# ethernet.net
KiCad netlist of a schematic drawn in Altium Designer
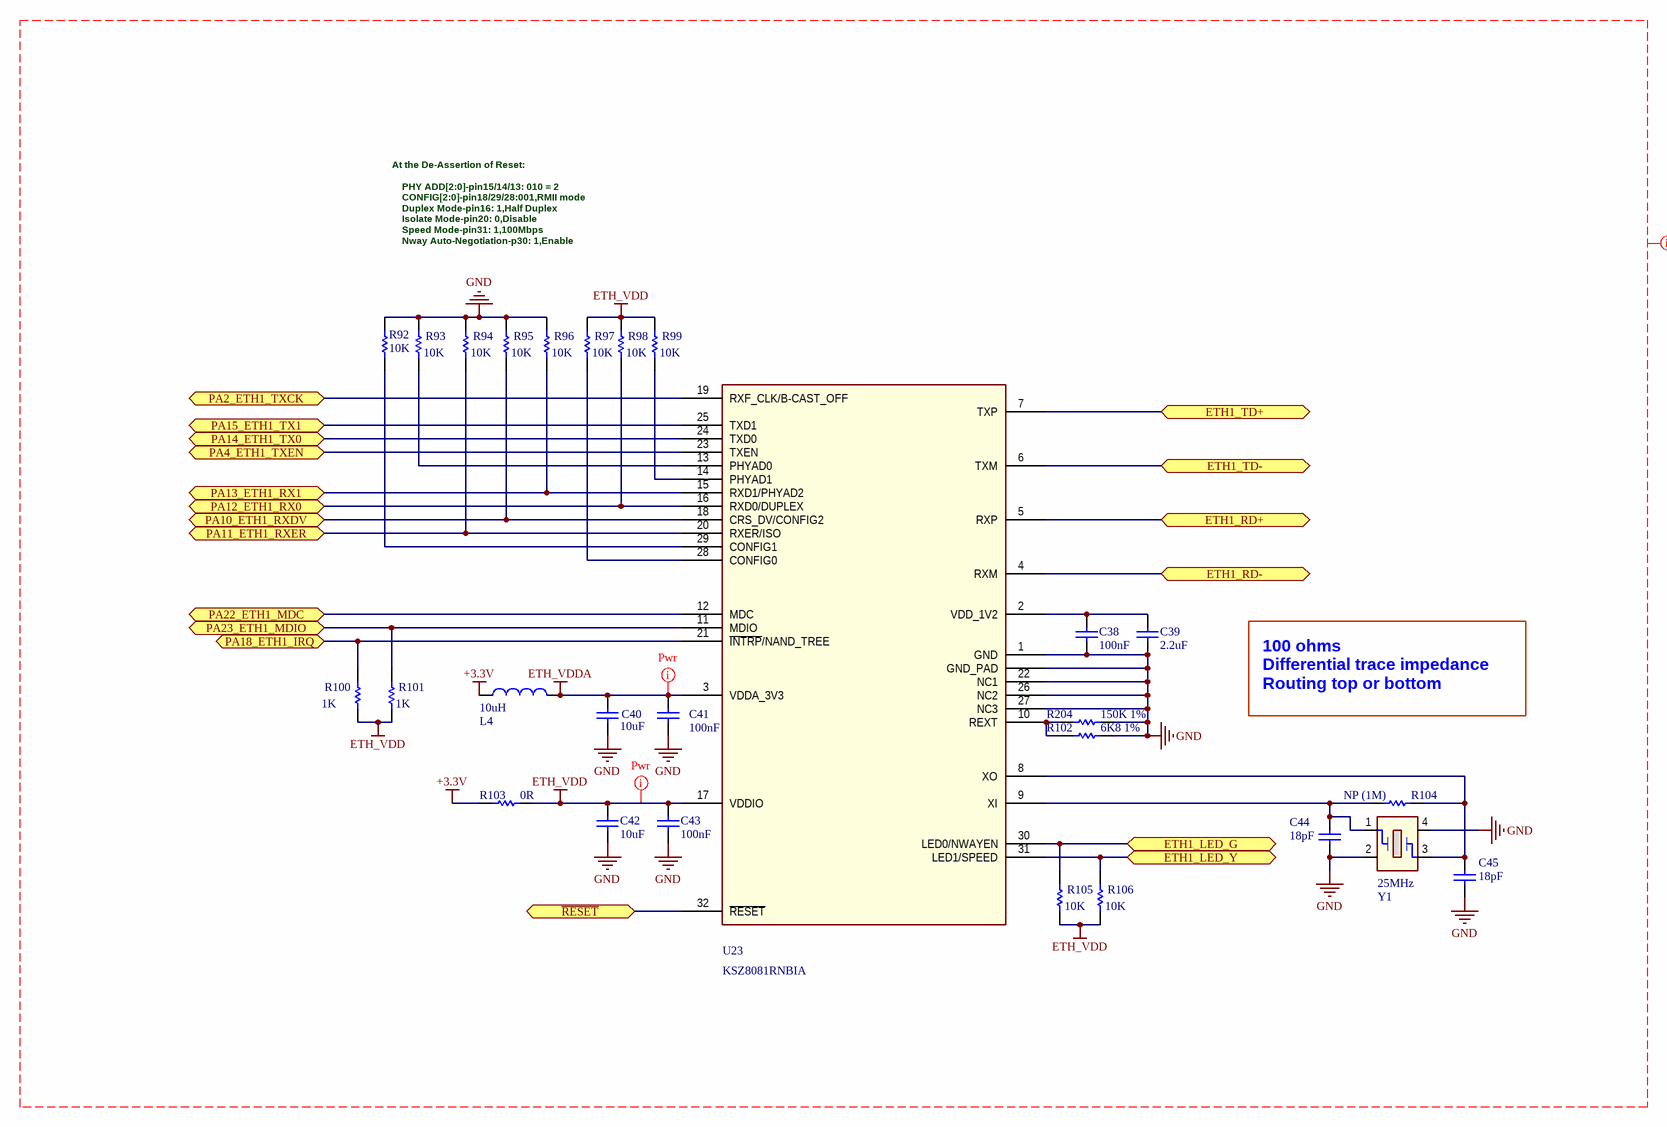
[diagram p0: ethernet.SchDoc]

(export (version "E")
  (design (tool "Eeschema 10.0.6"))
  (components
    (comp (ref "C38")
      (value "100nF")
      (footprint "0603_[1608]")
      (description "Ceramic X7R 50V")
      (fields (field (name "PUBLISHER") "Altium Limited"))
      (libsource (lib "project42_lib") (part "Cap"))
    )
    (comp (ref "C39")
      (value "2.2uF")
      (footprint "0603_[1608]")
      (description "Ceramic X7R, X5R 6.3V")
      (fields (field (name "PUBLISHER") "Altium Limited"))
      (libsource (lib "project42_lib") (part "Cap"))
    )
    (comp (ref "C40")
      (value "10uF")
      (footprint "1206_[3216]")
      (description "Ceramic X5R 25V")
      (fields (field (name "PUBLISHER") "Altium Limited"))
      (libsource (lib "project42_lib") (part "Cap"))
    )
    (comp (ref "C41")
      (value "100nF")
      (footprint "0603_[1608]")
      (description "Ceramic X7R 50V")
      (fields (field (name "PUBLISHER") "Altium Limited"))
      (libsource (lib "project42_lib") (part "Cap"))
    )
    (comp (ref "C42")
      (value "10uF")
      (footprint "1206_[3216]")
      (description "Ceramic X5R 25V")
      (fields (field (name "PUBLISHER") "Altium Limited"))
      (libsource (lib "project42_lib") (part "Cap"))
    )
    (comp (ref "C43")
      (value "100nF")
      (footprint "0603_[1608]")
      (description "Ceramic X7R 50V")
      (fields (field (name "PUBLISHER") "Altium Limited"))
      (libsource (lib "project42_lib") (part "Cap"))
    )
    (comp (ref "C44")
      (value "18pF")
      (footprint "0603_[1608]")
      (description "Ceraminc C0G/NP0 50V")
      (fields (field (name "PUBLISHER") "Altium Limited"))
      (libsource (lib "project42_lib") (part "Cap"))
    )
    (comp (ref "C45")
      (value "18pF")
      (footprint "0603_[1608]")
      (description "Ceraminc C0G/NP0 50V")
      (fields (field (name "PUBLISHER") "Altium Limited"))
      (libsource (lib "project42_lib") (part "Cap"))
    )
    (comp (ref "L4")
      (value "10uH")
      (footprint "0603_[1608]")
      (description "Inductor (MLZ1608N100L)")
      (fields (field (name "PUBLISHER") "Altium Limited"))
      (libsource (lib "DEVELER_Library") (part "Inductor"))
    )
    (comp (ref "R92")
      (value "10K")
      (footprint "0603_[1608]")
      (description "Resistor")
      (fields (field (name "PUBLISHER") "Altium Limited"))
      (libsource (lib "project42_lib") (part "Res1"))
    )
    (comp (ref "R93")
      (value "10K")
      (footprint "0603_[1608]")
      (description "Resistor")
      (fields (field (name "PUBLISHER") "Altium Limited"))
      (libsource (lib "project42_lib") (part "Res1"))
    )
    (comp (ref "R94")
      (value "10K")
      (footprint "0603_[1608]")
      (description "Resistor")
      (fields (field (name "PUBLISHER") "Altium Limited"))
      (libsource (lib "project42_lib") (part "Res1"))
    )
    (comp (ref "R95")
      (value "10K")
      (footprint "0603_[1608]")
      (description "Resistor")
      (fields (field (name "PUBLISHER") "Altium Limited"))
      (libsource (lib "project42_lib") (part "Res1"))
    )
    (comp (ref "R96")
      (value "10K")
      (footprint "0603_[1608]")
      (description "Resistor")
      (fields (field (name "PUBLISHER") "Altium Limited"))
      (libsource (lib "project42_lib") (part "Res1"))
    )
    (comp (ref "R97")
      (value "10K")
      (footprint "0603_[1608]")
      (description "Resistor")
      (fields (field (name "PUBLISHER") "Altium Limited"))
      (libsource (lib "project42_lib") (part "Res1"))
    )
    (comp (ref "R98")
      (value "10K")
      (footprint "0603_[1608]")
      (description "Resistor")
      (fields (field (name "PUBLISHER") "Altium Limited"))
      (libsource (lib "project42_lib") (part "Res1"))
    )
    (comp (ref "R99")
      (value "10K")
      (footprint "0603_[1608]")
      (description "Resistor")
      (fields (field (name "PUBLISHER") "Altium Limited"))
      (libsource (lib "project42_lib") (part "Res1"))
    )
    (comp (ref "R100")
      (value "1K")
      (footprint "0603_[1608]")
      (description "Resistor")
      (fields (field (name "PUBLISHER") "Altium Limited"))
      (libsource (lib "project42_lib") (part "Res1"))
    )
    (comp (ref "R101")
      (value "1K")
      (footprint "0603_[1608]")
      (description "Resistor")
      (fields (field (name "PUBLISHER") "Altium Limited"))
      (libsource (lib "project42_lib") (part "Res1"))
    )
    (comp (ref "R102")
      (value "6K8 1%")
      (footprint "0603_[1608]")
      (description "Resistor")
      (fields (field (name "PUBLISHER") "Altium Limited"))
      (libsource (lib "project42_lib") (part "Res1"))
    )
    (comp (ref "R103")
      (value "0R")
      (footprint "0603_[1608]")
      (description "Resistor")
      (fields (field (name "PUBLISHER") "Altium Limited"))
      (libsource (lib "project42_lib") (part "Res1"))
    )
    (comp (ref "R104")
      (value "NP (1M)")
      (footprint "0603_[1608]")
      (description "Resistor")
      (fields (field (name "PUBLISHER") "Altium Limited"))
      (libsource (lib "project42_lib") (part "Res1"))
    )
    (comp (ref "R105")
      (value "10K")
      (footprint "0603_[1608]")
      (description "Resistor")
      (fields (field (name "PUBLISHER") "Altium Limited"))
      (libsource (lib "project42_lib") (part "Res1"))
    )
    (comp (ref "R106")
      (value "10K")
      (footprint "0603_[1608]")
      (description "Resistor")
      (fields (field (name "PUBLISHER") "Altium Limited"))
      (libsource (lib "project42_lib") (part "Res1"))
    )
    (comp (ref "R204")
      (value "150K 1%")
      (footprint "0603_[1608]")
      (description "Resistor")
      (fields (field (name "PUBLISHER") "Altium Limited"))
      (libsource (lib "project42_lib") (part "Res1"))
    )
    (comp (ref "U23")
      (value "KSZ8081RNBIA")
      (footprint "QFN-32")
      (description "Ethernet PHY")
      (libsource (lib "project42_lib") (part "KSZ8081RNB"))
    )
    (comp (ref "Y1")
      (value "25MHz")
      (footprint "CRYSTAL_3.2X2.5MM_4P_SMD")
      (description "Crystal, Temperature -40C to +85C")
      (libsource (lib "project42_lib") (part "XTAL_13Y_A"))
    )
  )
  (nets
    (net (code "1") (name "+3.3V") (class "Default")
      (node (ref "L4") (pin "1") (pinfunction "1_1") (pintype "passive"))
      (node (ref "R103") (pin "2") (pinfunction "2_2") (pintype "passive"))
    )
    (net (code "2") (name "/ETH1_LED_G") (class "Default")
      (node (ref "R105") (pin "1") (pinfunction "1_1") (pintype "passive"))
      (node (ref "U23") (pin "30") (pinfunction "LED0/NWAYEN_30") (pintype "passive"))
    )
    (net (code "3") (name "/ETH1_LED_Y") (class "Default")
      (node (ref "R106") (pin "1") (pinfunction "1_1") (pintype "passive"))
      (node (ref "U23") (pin "31") (pinfunction "LED1/SPEED_31") (pintype "passive"))
    )
    (net (code "4") (name "/ETH1_RD+") (class "Default")
      (node (ref "U23") (pin "5") (pinfunction "RXP_5") (pintype "passive"))
    )
    (net (code "5") (name "/ETH1_RD-") (class "Default")
      (node (ref "U23") (pin "4") (pinfunction "RXM_4") (pintype "passive"))
    )
    (net (code "6") (name "/ETH1_TD+") (class "Default")
      (node (ref "U23") (pin "7") (pinfunction "TXP_7") (pintype "passive"))
    )
    (net (code "7") (name "/ETH1_TD-") (class "Default")
      (node (ref "U23") (pin "6") (pinfunction "TXM_6") (pintype "passive"))
    )
    (net (code "8") (name "/PA2_ETH1_TXCK") (class "Default")
      (node (ref "U23") (pin "19") (pinfunction "RXF_CLK/B-CAST_OFF_19") (pintype "passive"))
    )
    (net (code "9") (name "/PA4_ETH1_TXEN") (class "Default")
      (node (ref "U23") (pin "23") (pinfunction "TXEN_23") (pintype "passive"))
    )
    (net (code "10") (name "/PA10_ETH1_RXDV") (class "Default")
      (node (ref "R95") (pin "2") (pinfunction "2_2") (pintype "passive"))
      (node (ref "U23") (pin "18") (pinfunction "CRS_DV/CONFIG2_18") (pintype "passive"))
    )
    (net (code "11") (name "/PA11_ETH1_RXER") (class "Default")
      (node (ref "R94") (pin "2") (pinfunction "2_2") (pintype "passive"))
      (node (ref "U23") (pin "20") (pinfunction "RXER/ISO_20") (pintype "passive"))
    )
    (net (code "12") (name "/PA12_ETH1_RX0") (class "Default")
      (node (ref "R98") (pin "2") (pinfunction "2_2") (pintype "passive"))
      (node (ref "U23") (pin "16") (pinfunction "RXD0/DUPLEX_16") (pintype "passive"))
    )
    (net (code "13") (name "/PA13_ETH1_RX1") (class "Default")
      (node (ref "R96") (pin "2") (pinfunction "2_2") (pintype "passive"))
      (node (ref "U23") (pin "15") (pinfunction "RXD1/PHYAD2_15") (pintype "passive"))
    )
    (net (code "14") (name "/PA14_ETH1_TX0") (class "Default")
      (node (ref "U23") (pin "24") (pinfunction "TXD0_24") (pintype "passive"))
    )
    (net (code "15") (name "/PA15_ETH1_TX1") (class "Default")
      (node (ref "U23") (pin "25") (pinfunction "TXD1_25") (pintype "passive"))
    )
    (net (code "16") (name "/PA18_ETH1_IRQ") (class "Default")
      (node (ref "R100") (pin "1") (pinfunction "1_1") (pintype "passive"))
      (node (ref "U23") (pin "21") (pinfunction "~{INTRP}/NAND_TREE_21") (pintype "passive"))
    )
    (net (code "17") (name "/PA22_ETH1_MDC") (class "Default")
      (node (ref "U23") (pin "12") (pinfunction "MDC_12") (pintype "passive"))
    )
    (net (code "18") (name "/PA23_ETH1_MDIO") (class "Default")
      (node (ref "R101") (pin "1") (pinfunction "1_1") (pintype "passive"))
      (node (ref "U23") (pin "11") (pinfunction "MDIO_11") (pintype "passive"))
    )
    (net (code "19") (name "/RESET") (class "Default")
      (node (ref "U23") (pin "32") (pinfunction "~{RESET}_32") (pintype "passive"))
    )
    (net (code "20") (name "ETH_VDD") (class "Default")
      (node (ref "C42") (pin "2") (pinfunction "2_2") (pintype "passive"))
      (node (ref "C43") (pin "2") (pinfunction "2_2") (pintype "passive"))
      (node (ref "R100") (pin "2") (pinfunction "2_2") (pintype "passive"))
      (node (ref "R101") (pin "2") (pinfunction "2_2") (pintype "passive"))
      (node (ref "R103") (pin "1") (pinfunction "1_1") (pintype "passive"))
      (node (ref "R105") (pin "2") (pinfunction "2_2") (pintype "passive"))
      (node (ref "R106") (pin "2") (pinfunction "2_2") (pintype "passive"))
      (node (ref "R97") (pin "1") (pinfunction "1_1") (pintype "passive"))
      (node (ref "R98") (pin "1") (pinfunction "1_1") (pintype "passive"))
      (node (ref "R99") (pin "1") (pinfunction "1_1") (pintype "passive"))
      (node (ref "U23") (pin "17") (pinfunction "VDDIO_17") (pintype "passive"))
    )
    (net (code "21") (name "ETH_VDDA") (class "Default")
      (node (ref "C40") (pin "2") (pinfunction "2_2") (pintype "passive"))
      (node (ref "C41") (pin "2") (pinfunction "2_2") (pintype "passive"))
      (node (ref "L4") (pin "2") (pinfunction "2_2") (pintype "passive"))
      (node (ref "U23") (pin "3") (pinfunction "VDDA_3V3_3") (pintype "passive"))
    )
    (net (code "22") (name "GND") (class "Default")
      (node (ref "C38") (pin "1") (pinfunction "1_1") (pintype "passive"))
      (node (ref "C39") (pin "1") (pinfunction "1_1") (pintype "passive"))
      (node (ref "C40") (pin "1") (pinfunction "1_1") (pintype "passive"))
      (node (ref "C41") (pin "1") (pinfunction "1_1") (pintype "passive"))
      (node (ref "C42") (pin "1") (pinfunction "1_1") (pintype "passive"))
      (node (ref "C43") (pin "1") (pinfunction "1_1") (pintype "passive"))
      (node (ref "C44") (pin "1") (pinfunction "1_1") (pintype "passive"))
      (node (ref "C45") (pin "1") (pinfunction "1_1") (pintype "passive"))
      (node (ref "R102") (pin "2") (pinfunction "2_2") (pintype "passive"))
      (node (ref "R204") (pin "2") (pinfunction "2_2") (pintype "passive"))
      (node (ref "R92") (pin "2") (pinfunction "2_2") (pintype "passive"))
      (node (ref "R93") (pin "1") (pinfunction "1_1") (pintype "passive"))
      (node (ref "R94") (pin "1") (pinfunction "1_1") (pintype "passive"))
      (node (ref "R95") (pin "1") (pinfunction "1_1") (pintype "passive"))
      (node (ref "R96") (pin "1") (pinfunction "1_1") (pintype "passive"))
      (node (ref "U23") (pin "1") (pinfunction "GND_1") (pintype "passive"))
      (node (ref "U23") (pin "22") (pinfunction "NC1_22") (pintype "passive"))
      (node (ref "U23") (pin "26") (pinfunction "NC2_26") (pintype "passive"))
      (node (ref "U23") (pin "27") (pinfunction "NC3_27") (pintype "passive"))
      (node (ref "U23") (pin "GND_PAD") (pinfunction "GND_PAD_GND_PAD") (pintype "passive"))
      (node (ref "Y1") (pin "2") (pinfunction "2_2") (pintype "passive"))
      (node (ref "Y1") (pin "4") (pinfunction "4_4") (pintype "passive"))
    )
    (net (code "23") (name "Net-(U23-CONFIG0)") (class "Default")
      (node (ref "R97") (pin "2") (pinfunction "2_2") (pintype "passive"))
      (node (ref "U23") (pin "28") (pinfunction "CONFIG0_28") (pintype "passive"))
    )
    (net (code "24") (name "Net-(U23-CONFIG1)") (class "Default")
      (node (ref "R92") (pin "1") (pinfunction "1_1") (pintype "passive"))
      (node (ref "U23") (pin "29") (pinfunction "CONFIG1_29") (pintype "passive"))
    )
    (net (code "25") (name "Net-(U23-PHYAD0)") (class "Default")
      (node (ref "R93") (pin "2") (pinfunction "2_2") (pintype "passive"))
      (node (ref "U23") (pin "13") (pinfunction "PHYAD0_13") (pintype "passive"))
    )
    (net (code "26") (name "Net-(U23-PHYAD1)") (class "Default")
      (node (ref "R99") (pin "2") (pinfunction "2_2") (pintype "passive"))
      (node (ref "U23") (pin "14") (pinfunction "PHYAD1_14") (pintype "passive"))
    )
    (net (code "27") (name "Net-(U23-REXT)") (class "Default")
      (node (ref "R102") (pin "1") (pinfunction "1_1") (pintype "passive"))
      (node (ref "R204") (pin "1") (pinfunction "1_1") (pintype "passive"))
      (node (ref "U23") (pin "10") (pinfunction "REXT_10") (pintype "passive"))
    )
    (net (code "28") (name "Net-(U23-VDD_1V2)") (class "Default")
      (node (ref "C38") (pin "2") (pinfunction "2_2") (pintype "passive"))
      (node (ref "C39") (pin "2") (pinfunction "2_2") (pintype "passive"))
      (node (ref "U23") (pin "2") (pinfunction "VDD_1V2_2") (pintype "passive"))
    )
    (net (code "29") (name "Net-(U23-XI)") (class "Default")
      (node (ref "C44") (pin "2") (pinfunction "2_2") (pintype "passive"))
      (node (ref "R104") (pin "2") (pinfunction "2_2") (pintype "passive"))
      (node (ref "U23") (pin "9") (pinfunction "XI_9") (pintype "passive"))
      (node (ref "Y1") (pin "1") (pinfunction "1_1") (pintype "passive"))
    )
    (net (code "30") (name "Net-(U23-XO)") (class "Default")
      (node (ref "C45") (pin "2") (pinfunction "2_2") (pintype "passive"))
      (node (ref "R104") (pin "1") (pinfunction "1_1") (pintype "passive"))
      (node (ref "U23") (pin "8") (pinfunction "XO_8") (pintype "passive"))
      (node (ref "Y1") (pin "3") (pinfunction "3_3") (pintype "passive"))
    )
  )
)
